# Shels_System_ADP.net
KiCad netlist of a schematic drawn in Altium Designer
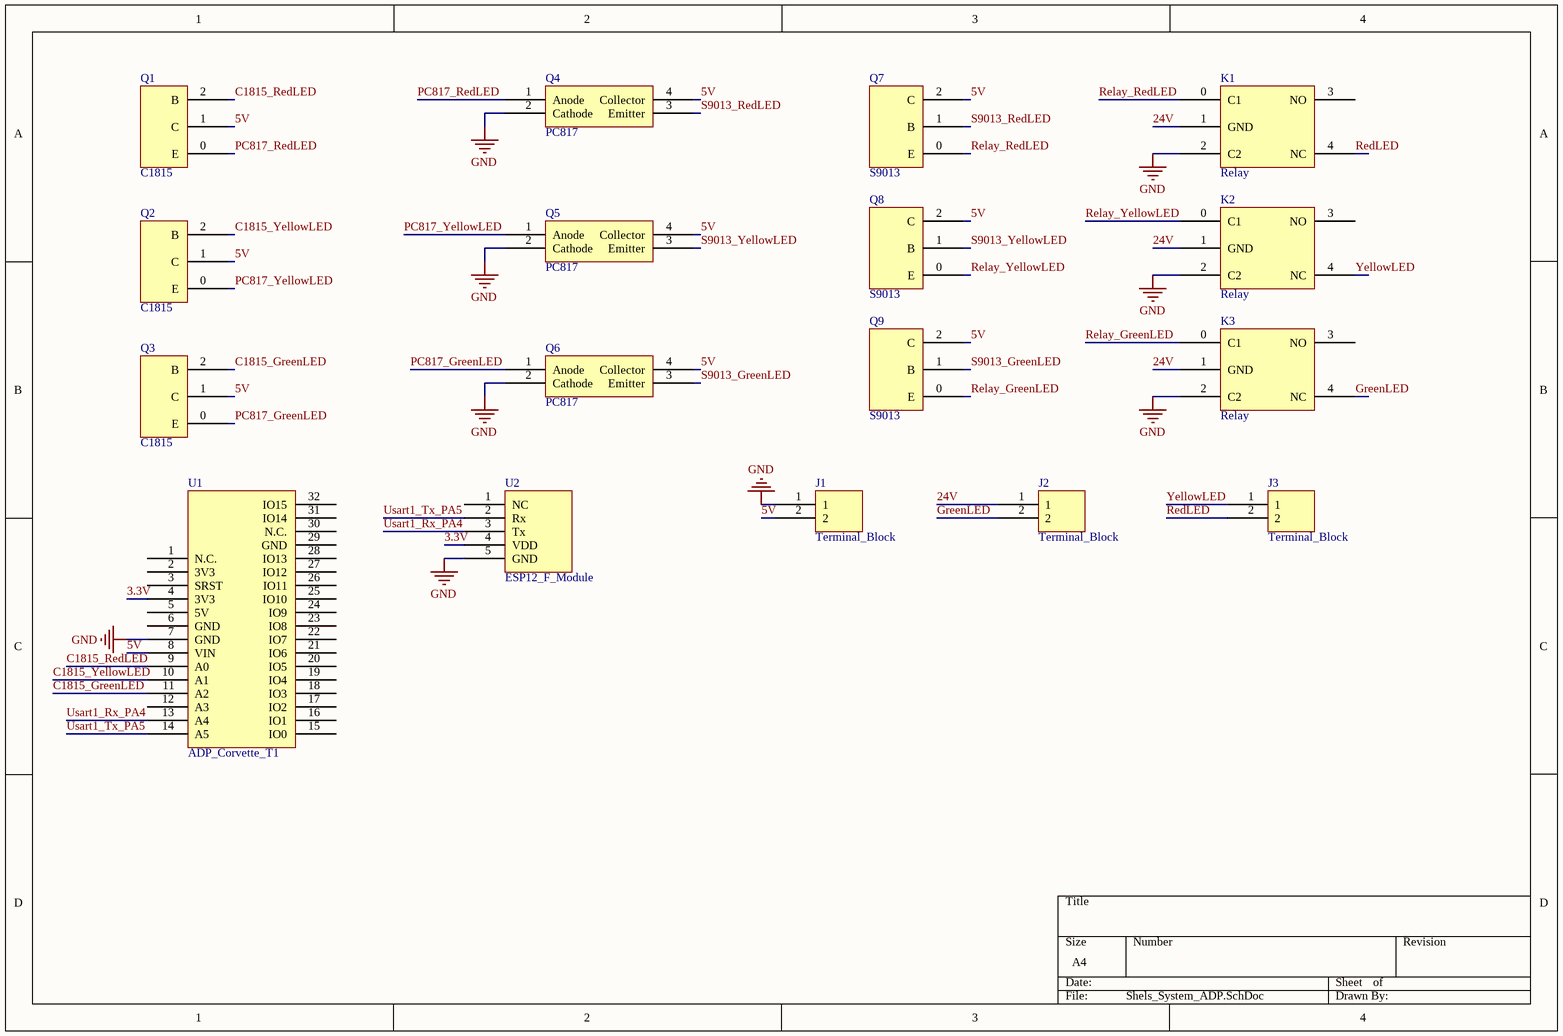
[diagram p0: Shels_System_ADP.SchDoc]

(export (version "E")
  (design (tool "Eeschema 10.0.6"))
  (components
    (comp (ref "J1")
      (value "Terminal_Block")
      (footprint "terminal block")
      (libsource (lib "Lab_share") (part "Terminal Block"))
    )
    (comp (ref "J2")
      (value "Terminal_Block")
      (footprint "terminal block")
      (libsource (lib "Lab_share") (part "Terminal Block"))
    )
    (comp (ref "J3")
      (value "Terminal_Block")
      (footprint "terminal block")
      (libsource (lib "Lab_share") (part "Terminal Block"))
    )
    (comp (ref "K1") (value "Relay") (footprint "Relay") (libsource (lib "Lab_share") (part "Relay")))
    (comp (ref "K2") (value "Relay") (footprint "Relay") (libsource (lib "Lab_share") (part "Relay")))
    (comp (ref "K3") (value "Relay") (footprint "Relay") (libsource (lib "Lab_share") (part "Relay")))
    (comp (ref "Q1") (value "C1815") (footprint "C1815") (libsource (lib "Lab_share") (part "C1815")))
    (comp (ref "Q2") (value "C1815") (footprint "C1815") (libsource (lib "Lab_share") (part "C1815")))
    (comp (ref "Q3") (value "C1815") (footprint "C1815") (libsource (lib "Lab_share") (part "C1815")))
    (comp (ref "Q4") (value "PC817") (footprint "PC817") (libsource (lib "Lab_share") (part "PC817")))
    (comp (ref "Q5") (value "PC817") (footprint "PC817") (libsource (lib "Lab_share") (part "PC817")))
    (comp (ref "Q6") (value "PC817") (footprint "PC817") (libsource (lib "Lab_share") (part "PC817")))
    (comp (ref "Q7") (value "S9013") (footprint "S9013") (libsource (lib "Lab_share") (part "S9013")))
    (comp (ref "Q8") (value "S9013") (footprint "S9013") (libsource (lib "Lab_share") (part "S9013")))
    (comp (ref "Q9") (value "S9013") (footprint "S9013") (libsource (lib "Lab_share") (part "S9013")))
    (comp (ref "U1")
      (value "ADP_Corvette_T1")
      (footprint "Corvette_T1")
      (libsource (lib "Lab_share") (part "Corvette_T1"))
    )
    (comp (ref "U2")
      (value "ESP12_F_Module")
      (footprint "ESP12_F_Holtek")
      (libsource (lib "Lab_share") (part "ESP12_F_Holtek"))
    )
  )
  (nets
    (net (code "1") (name "/3.3V") (class "Default")
      (node (ref "U1") (pin "4") (pinfunction "3V3_4") (pintype "passive"))
      (node (ref "U2") (pin "4") (pinfunction "VDD_4") (pintype "passive"))
    )
    (net (code "2") (name "/5V") (class "Default")
      (node (ref "J1") (pin "2") (pinfunction "2_2") (pintype "passive"))
      (node (ref "Q1") (pin "1") (pinfunction "C_1") (pintype "passive"))
      (node (ref "Q2") (pin "1") (pinfunction "C_1") (pintype "passive"))
      (node (ref "Q3") (pin "1") (pinfunction "C_1") (pintype "passive"))
      (node (ref "Q4") (pin "4") (pinfunction "Collector_4") (pintype "passive"))
      (node (ref "Q5") (pin "4") (pinfunction "Collector_4") (pintype "passive"))
      (node (ref "Q6") (pin "4") (pinfunction "Collector_4") (pintype "passive"))
      (node (ref "Q7") (pin "2") (pinfunction "C_2") (pintype "passive"))
      (node (ref "Q8") (pin "2") (pinfunction "C_2") (pintype "passive"))
      (node (ref "Q9") (pin "2") (pinfunction "C_2") (pintype "passive"))
      (node (ref "U1") (pin "8") (pinfunction "VIN_8") (pintype "passive"))
    )
    (net (code "3") (name "/24V") (class "Default")
      (node (ref "J2") (pin "1") (pinfunction "1_1") (pintype "passive"))
      (node (ref "K1") (pin "1") (pinfunction "GND_1") (pintype "passive"))
      (node (ref "K2") (pin "1") (pinfunction "GND_1") (pintype "passive"))
      (node (ref "K3") (pin "1") (pinfunction "GND_1") (pintype "passive"))
    )
    (net (code "4") (name "/C1815_GreenLED") (class "Default")
      (node (ref "Q3") (pin "2") (pinfunction "B_2") (pintype "passive"))
      (node (ref "U1") (pin "11") (pinfunction "A2_11") (pintype "passive"))
    )
    (net (code "5") (name "/C1815_RedLED") (class "Default")
      (node (ref "Q1") (pin "2") (pinfunction "B_2") (pintype "passive"))
      (node (ref "U1") (pin "9") (pinfunction "A0_9") (pintype "passive"))
    )
    (net (code "6") (name "/C1815_YellowLED") (class "Default")
      (node (ref "Q2") (pin "2") (pinfunction "B_2") (pintype "passive"))
      (node (ref "U1") (pin "10") (pinfunction "A1_10") (pintype "passive"))
    )
    (net (code "7") (name "/GreenLED") (class "Default")
      (node (ref "J2") (pin "2") (pinfunction "2_2") (pintype "passive"))
      (node (ref "K3") (pin "4") (pinfunction "NC_4") (pintype "passive"))
    )
    (net (code "8") (name "/PC817_GreenLED") (class "Default")
      (node (ref "Q3") (pin "0") (pinfunction "E_0") (pintype "passive"))
      (node (ref "Q6") (pin "1") (pinfunction "Anode_1") (pintype "passive"))
    )
    (net (code "9") (name "/PC817_RedLED") (class "Default")
      (node (ref "Q1") (pin "0") (pinfunction "E_0") (pintype "passive"))
      (node (ref "Q4") (pin "1") (pinfunction "Anode_1") (pintype "passive"))
    )
    (net (code "10") (name "/PC817_YellowLED") (class "Default")
      (node (ref "Q2") (pin "0") (pinfunction "E_0") (pintype "passive"))
      (node (ref "Q5") (pin "1") (pinfunction "Anode_1") (pintype "passive"))
    )
    (net (code "11") (name "/RedLED") (class "Default")
      (node (ref "J3") (pin "2") (pinfunction "2_2") (pintype "passive"))
      (node (ref "K1") (pin "4") (pinfunction "NC_4") (pintype "passive"))
    )
    (net (code "12") (name "/Relay_GreenLED") (class "Default")
      (node (ref "K3") (pin "0") (pinfunction "C1_0") (pintype "passive"))
      (node (ref "Q9") (pin "0") (pinfunction "E_0") (pintype "passive"))
    )
    (net (code "13") (name "/Relay_RedLED") (class "Default")
      (node (ref "K1") (pin "0") (pinfunction "C1_0") (pintype "passive"))
      (node (ref "Q7") (pin "0") (pinfunction "E_0") (pintype "passive"))
    )
    (net (code "14") (name "/Relay_YellowLED") (class "Default")
      (node (ref "K2") (pin "0") (pinfunction "C1_0") (pintype "passive"))
      (node (ref "Q8") (pin "0") (pinfunction "E_0") (pintype "passive"))
    )
    (net (code "15") (name "/S9013_GreenLED") (class "Default")
      (node (ref "Q6") (pin "3") (pinfunction "Emitter_3") (pintype "passive"))
      (node (ref "Q9") (pin "1") (pinfunction "B_1") (pintype "passive"))
    )
    (net (code "16") (name "/S9013_RedLED") (class "Default")
      (node (ref "Q4") (pin "3") (pinfunction "Emitter_3") (pintype "passive"))
      (node (ref "Q7") (pin "1") (pinfunction "B_1") (pintype "passive"))
    )
    (net (code "17") (name "/S9013_YellowLED") (class "Default")
      (node (ref "Q5") (pin "3") (pinfunction "Emitter_3") (pintype "passive"))
      (node (ref "Q8") (pin "1") (pinfunction "B_1") (pintype "passive"))
    )
    (net (code "18") (name "/Usart1_Rx_PA4") (class "Default")
      (node (ref "U1") (pin "13") (pinfunction "A4_13") (pintype "passive"))
      (node (ref "U2") (pin "3") (pinfunction "Tx_3") (pintype "passive"))
    )
    (net (code "19") (name "/Usart1_Tx_PA5") (class "Default")
      (node (ref "U1") (pin "14") (pinfunction "A5_14") (pintype "passive"))
      (node (ref "U2") (pin "2") (pinfunction "Rx_2") (pintype "passive"))
    )
    (net (code "20") (name "/YellowLED") (class "Default")
      (node (ref "J3") (pin "1") (pinfunction "1_1") (pintype "passive"))
      (node (ref "K2") (pin "4") (pinfunction "NC_4") (pintype "passive"))
    )
    (net (code "21") (name "GND") (class "Default")
      (node (ref "J1") (pin "1") (pinfunction "1_1") (pintype "passive"))
      (node (ref "K1") (pin "2") (pinfunction "C2_2") (pintype "passive"))
      (node (ref "K2") (pin "2") (pinfunction "C2_2") (pintype "passive"))
      (node (ref "K3") (pin "2") (pinfunction "C2_2") (pintype "passive"))
      (node (ref "Q4") (pin "2") (pinfunction "Cathode_2") (pintype "passive"))
      (node (ref "Q5") (pin "2") (pinfunction "Cathode_2") (pintype "passive"))
      (node (ref "Q6") (pin "2") (pinfunction "Cathode_2") (pintype "passive"))
      (node (ref "U1") (pin "7") (pinfunction "GND_7") (pintype "passive"))
      (node (ref "U2") (pin "5") (pinfunction "GND_5") (pintype "passive"))
    )
    (net (code "22") (name "unconnected-(K1-NO-Pad3)") (class "Default")
      (node (ref "K1") (pin "3") (pinfunction "NO_3") (pintype "passive"))
    )
    (net (code "23") (name "unconnected-(K2-NO-Pad3)") (class "Default")
      (node (ref "K2") (pin "3") (pinfunction "NO_3") (pintype "passive"))
    )
    (net (code "24") (name "unconnected-(K3-NO-Pad3)") (class "Default")
      (node (ref "K3") (pin "3") (pinfunction "NO_3") (pintype "passive"))
    )
    (net (code "25") (name "unconnected-(U1-3V3-Pad2)") (class "Default")
      (node (ref "U1") (pin "2") (pinfunction "3V3_2") (pintype "passive"))
    )
    (net (code "26") (name "unconnected-(U1-5V-Pad5)") (class "Default")
      (node (ref "U1") (pin "5") (pinfunction "5V_5") (pintype "passive"))
    )
    (net (code "27") (name "unconnected-(U1-A3-Pad12)") (class "Default")
      (node (ref "U1") (pin "12") (pinfunction "A3_12") (pintype "passive"))
    )
    (net (code "28") (name "unconnected-(U1-GND-Pad6)") (class "Default")
      (node (ref "U1") (pin "6") (pinfunction "GND_6") (pintype "passive"))
    )
    (net (code "29") (name "unconnected-(U1-GND-Pad29)") (class "Default")
      (node (ref "U1") (pin "29") (pinfunction "GND_29") (pintype "passive"))
    )
    (net (code "30") (name "unconnected-(U1-IO0-Pad15)") (class "Default")
      (node (ref "U1") (pin "15") (pinfunction "IO0_15") (pintype "passive"))
    )
    (net (code "31") (name "unconnected-(U1-IO1-Pad16)") (class "Default")
      (node (ref "U1") (pin "16") (pinfunction "IO1_16") (pintype "passive"))
    )
    (net (code "32") (name "unconnected-(U1-IO2-Pad17)") (class "Default")
      (node (ref "U1") (pin "17") (pinfunction "IO2_17") (pintype "passive"))
    )
    (net (code "33") (name "unconnected-(U1-IO3-Pad18)") (class "Default")
      (node (ref "U1") (pin "18") (pinfunction "IO3_18") (pintype "passive"))
    )
    (net (code "34") (name "unconnected-(U1-IO4-Pad19)") (class "Default")
      (node (ref "U1") (pin "19") (pinfunction "IO4_19") (pintype "passive"))
    )
    (net (code "35") (name "unconnected-(U1-IO5-Pad20)") (class "Default")
      (node (ref "U1") (pin "20") (pinfunction "IO5_20") (pintype "passive"))
    )
    (net (code "36") (name "unconnected-(U1-IO6-Pad21)") (class "Default")
      (node (ref "U1") (pin "21") (pinfunction "IO6_21") (pintype "passive"))
    )
    (net (code "37") (name "unconnected-(U1-IO7-Pad22)") (class "Default")
      (node (ref "U1") (pin "22") (pinfunction "IO7_22") (pintype "passive"))
    )
    (net (code "38") (name "unconnected-(U1-IO8-Pad23)") (class "Default")
      (node (ref "U1") (pin "23") (pinfunction "IO8_23") (pintype "passive"))
    )
    (net (code "39") (name "unconnected-(U1-IO9-Pad24)") (class "Default")
      (node (ref "U1") (pin "24") (pinfunction "IO9_24") (pintype "passive"))
    )
    (net (code "40") (name "unconnected-(U1-IO10-Pad25)") (class "Default")
      (node (ref "U1") (pin "25") (pinfunction "IO10_25") (pintype "passive"))
    )
    (net (code "41") (name "unconnected-(U1-IO11-Pad26)") (class "Default")
      (node (ref "U1") (pin "26") (pinfunction "IO11_26") (pintype "passive"))
    )
    (net (code "42") (name "unconnected-(U1-IO12-Pad27)") (class "Default")
      (node (ref "U1") (pin "27") (pinfunction "IO12_27") (pintype "passive"))
    )
    (net (code "43") (name "unconnected-(U1-IO13-Pad28)") (class "Default")
      (node (ref "U1") (pin "28") (pinfunction "IO13_28") (pintype "passive"))
    )
    (net (code "44") (name "unconnected-(U1-IO14-Pad31)") (class "Default")
      (node (ref "U1") (pin "31") (pinfunction "IO14_31") (pintype "passive"))
    )
    (net (code "45") (name "unconnected-(U1-IO15-Pad32)") (class "Default")
      (node (ref "U1") (pin "32") (pinfunction "IO15_32") (pintype "passive"))
    )
    (net (code "46") (name "unconnected-(U1-N.C.-Pad1)") (class "Default")
      (node (ref "U1") (pin "1") (pinfunction "N.C._1") (pintype "passive"))
    )
    (net (code "47") (name "unconnected-(U1-N.C.-Pad30)") (class "Default")
      (node (ref "U1") (pin "30") (pinfunction "N.C._30") (pintype "passive"))
    )
    (net (code "48") (name "unconnected-(U1-SRST-Pad3)") (class "Default")
      (node (ref "U1") (pin "3") (pinfunction "SRST_3") (pintype "passive"))
    )
    (net (code "49") (name "unconnected-(U2-NC-Pad1)") (class "Default")
      (node (ref "U2") (pin "1") (pinfunction "NC_1") (pintype "passive"))
    )
  )
)
